# Power_Board_CRoach.net
KiCad netlist of a schematic drawn in EAGLE
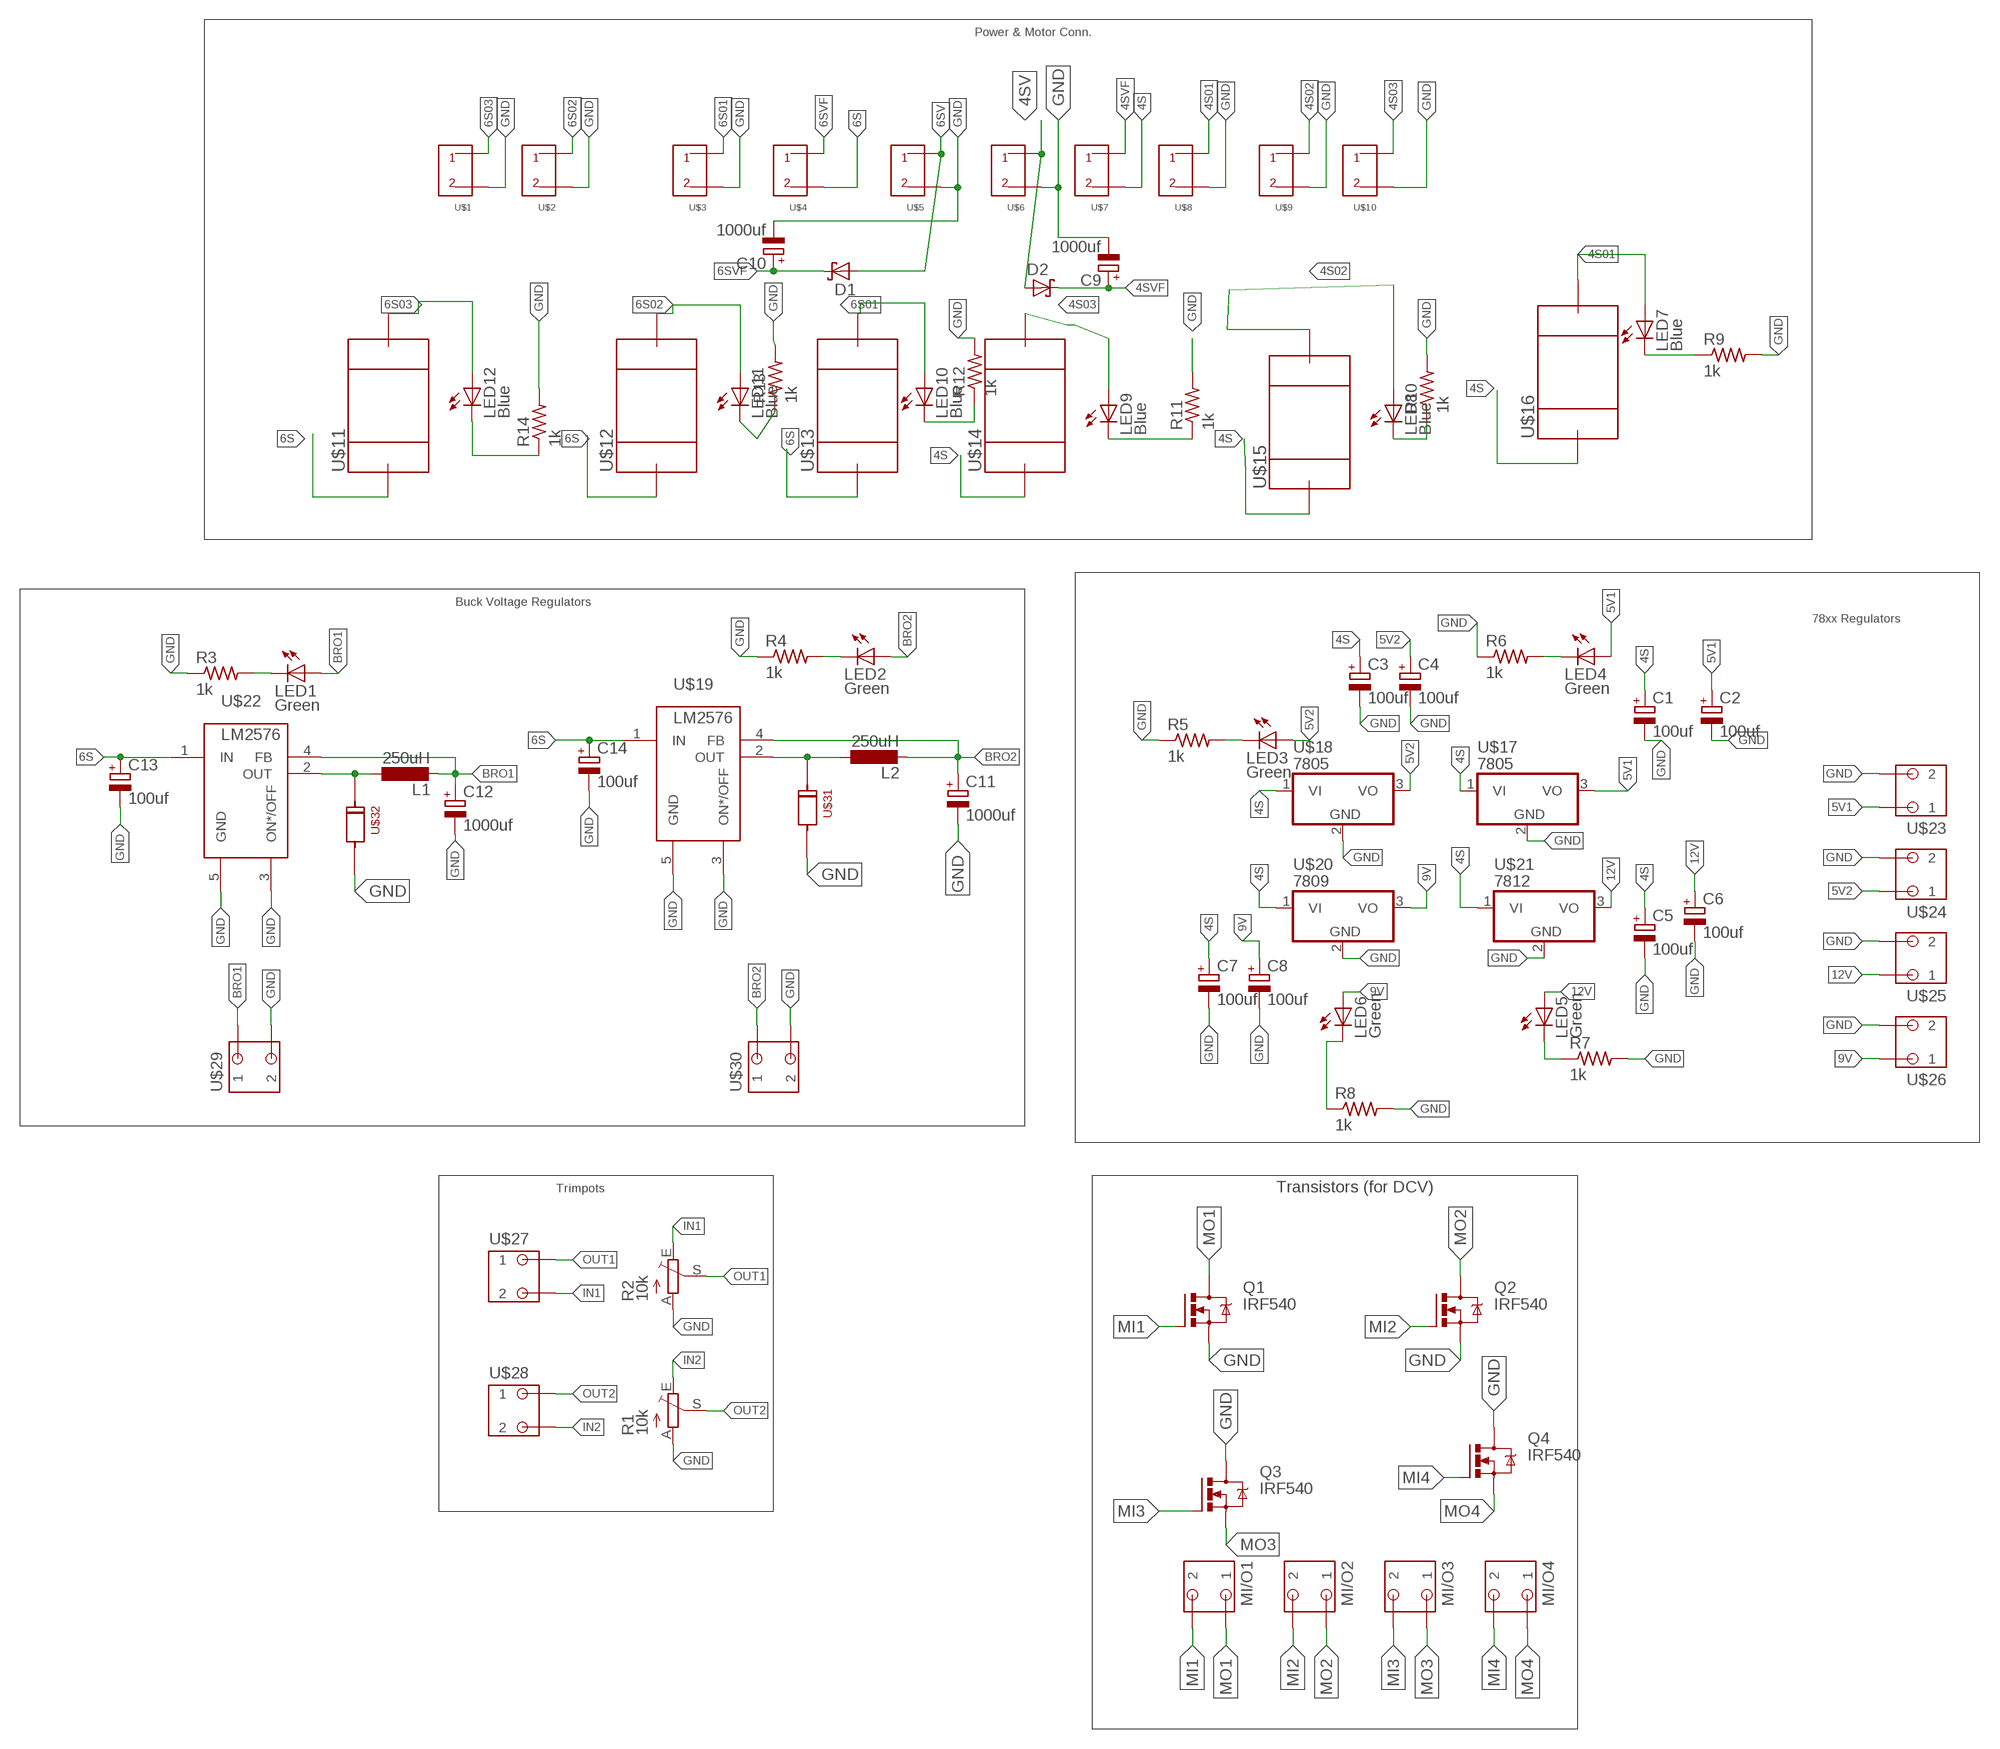
[diagram p0: schematic, sheet 1]

(export (version "E")
  (design (tool "Eeschema 10.0.6"))
  (components
    (comp (ref "C1")
      (value "100uf")
      (footprint "eagle-import:E2-5")
      (libsource (lib "eagle-import") (part "CPOL-EUE2-5"))
    )
    (comp (ref "C2")
      (value "100uf")
      (footprint "eagle-import:E2-5")
      (libsource (lib "eagle-import") (part "CPOL-EUE2-5"))
    )
    (comp (ref "C3")
      (value "100uf")
      (footprint "eagle-import:E2-5")
      (libsource (lib "eagle-import") (part "CPOL-EUE2-5"))
    )
    (comp (ref "C4")
      (value "100uf")
      (footprint "eagle-import:E2-5")
      (libsource (lib "eagle-import") (part "CPOL-EUE2-5"))
    )
    (comp (ref "C5")
      (value "100uf")
      (footprint "eagle-import:E2-5")
      (libsource (lib "eagle-import") (part "CPOL-EUE2-5"))
    )
    (comp (ref "C6")
      (value "100uf")
      (footprint "eagle-import:E2-5")
      (libsource (lib "eagle-import") (part "CPOL-EUE2-5"))
    )
    (comp (ref "C7")
      (value "100uf")
      (footprint "eagle-import:E2-5")
      (libsource (lib "eagle-import") (part "CPOL-EUE2-5"))
    )
    (comp (ref "C8")
      (value "100uf")
      (footprint "eagle-import:E2-5")
      (libsource (lib "eagle-import") (part "CPOL-EUE2-5"))
    )
    (comp (ref "C9")
      (value "1000uf")
      (footprint "eagle-import:E7,5-16")
      (libsource (lib "eagle-import") (part "CPOL-EUE7.5-16"))
    )
    (comp (ref "C10")
      (value "1000uf")
      (footprint "eagle-import:E7,5-16")
      (libsource (lib "eagle-import") (part "CPOL-EUE7.5-16"))
    )
    (comp (ref "C11")
      (value "1000uf")
      (footprint "eagle-import:E7,5-16")
      (libsource (lib "eagle-import") (part "CPOL-EUE7.5-16"))
    )
    (comp (ref "C12")
      (value "1000uf")
      (footprint "eagle-import:E7,5-16")
      (libsource (lib "eagle-import") (part "CPOL-EUE7.5-16"))
    )
    (comp (ref "C13")
      (value "100uf")
      (footprint "eagle-import:E2,5-5")
      (libsource (lib "eagle-import") (part "CPOL-EUE2.5-5"))
    )
    (comp (ref "C14")
      (value "100uf")
      (footprint "eagle-import:E2,5-5")
      (libsource (lib "eagle-import") (part "CPOL-EUE2.5-5"))
    )
    (comp (ref "D1")
      (value "SCHOTTKY-DIODEP6T15")
      (footprint "eagle-import:P6T15")
      (libsource (lib "eagle-import") (part "SCHOTTKY-DIODEP6T15"))
    )
    (comp (ref "D2")
      (value "SCHOTTKY-DIODEP6T15")
      (footprint "eagle-import:P6T15")
      (libsource (lib "eagle-import") (part "SCHOTTKY-DIODEP6T15"))
    )
    (comp (ref "L1")
      (value "250uH")
      (footprint "eagle-import:0204_7")
      (libsource (lib "eagle-import") (part "L-EU0204/7"))
    )
    (comp (ref "L2")
      (value "250uH")
      (footprint "eagle-import:0204_7")
      (libsource (lib "eagle-import") (part "L-EU0204/7"))
    )
    (comp (ref "LED1")
      (value "Green")
      (footprint "eagle-import:LED5MM")
      (libsource (lib "eagle-import") (part "LED5MM"))
    )
    (comp (ref "LED2")
      (value "Green")
      (footprint "eagle-import:LED5MM")
      (libsource (lib "eagle-import") (part "LED5MM"))
    )
    (comp (ref "LED3")
      (value "Green")
      (footprint "eagle-import:LED5MM")
      (libsource (lib "eagle-import") (part "LED5MM"))
    )
    (comp (ref "LED4")
      (value "Green")
      (footprint "eagle-import:LED5MM")
      (libsource (lib "eagle-import") (part "LED5MM"))
    )
    (comp (ref "LED5")
      (value "Green")
      (footprint "eagle-import:LED5MM")
      (libsource (lib "eagle-import") (part "LED5MM"))
    )
    (comp (ref "LED6")
      (value "Green")
      (footprint "eagle-import:LED5MM")
      (libsource (lib "eagle-import") (part "LED5MM"))
    )
    (comp (ref "LED7")
      (value "Blue")
      (footprint "eagle-import:LED5MM")
      (libsource (lib "eagle-import") (part "LED5MM"))
    )
    (comp (ref "LED8")
      (value "Blue")
      (footprint "eagle-import:LED5MM")
      (libsource (lib "eagle-import") (part "LED5MM"))
    )
    (comp (ref "LED9")
      (value "Blue")
      (footprint "eagle-import:LED5MM")
      (libsource (lib "eagle-import") (part "LED5MM"))
    )
    (comp (ref "LED10")
      (value "Blue")
      (footprint "eagle-import:LED5MM")
      (libsource (lib "eagle-import") (part "LED5MM"))
    )
    (comp (ref "LED11")
      (value "Blue")
      (footprint "eagle-import:LED5MM")
      (libsource (lib "eagle-import") (part "LED5MM"))
    )
    (comp (ref "LED12")
      (value "Blue")
      (footprint "eagle-import:LED5MM")
      (libsource (lib "eagle-import") (part "LED5MM"))
    )
    (comp (ref "MI/O1")
      (value "SPTBB2-A2")
      (footprint "eagle-import:SPTB")
      (libsource (lib "eagle-import") (part "SPTBB2-A2"))
    )
    (comp (ref "MI/O2")
      (value "SPTBB2-A2")
      (footprint "eagle-import:SPTB")
      (libsource (lib "eagle-import") (part "SPTBB2-A2"))
    )
    (comp (ref "MI/O3")
      (value "SPTBB2-A2")
      (footprint "eagle-import:SPTB")
      (libsource (lib "eagle-import") (part "SPTBB2-A2"))
    )
    (comp (ref "MI/O4")
      (value "SPTBB2-A2")
      (footprint "eagle-import:SPTB")
      (libsource (lib "eagle-import") (part "SPTBB2-A2"))
    )
    (comp (ref "Q1")
      (value "IRF540")
      (footprint "eagle-import:TO220BV")
      (libsource (lib "eagle-import") (part "IRF540"))
    )
    (comp (ref "Q2")
      (value "IRF540")
      (footprint "eagle-import:TO220BV")
      (libsource (lib "eagle-import") (part "IRF540"))
    )
    (comp (ref "Q3")
      (value "IRF540")
      (footprint "eagle-import:TO220BV")
      (libsource (lib "eagle-import") (part "IRF540"))
    )
    (comp (ref "Q4")
      (value "IRF540")
      (footprint "eagle-import:TO220BV")
      (libsource (lib "eagle-import") (part "IRF540"))
    )
    (comp (ref "R1")
      (value "10k")
      (footprint "eagle-import:CA6V")
      (libsource (lib "eagle-import") (part "TRIM_EU-CA6V"))
    )
    (comp (ref "R2")
      (value "10k")
      (footprint "eagle-import:CA6V")
      (libsource (lib "eagle-import") (part "TRIM_EU-CA6V"))
    )
    (comp (ref "R3")
      (value "1k")
      (footprint "eagle-import:0204_7")
      (libsource (lib "eagle-import") (part "R-US_0204/7"))
    )
    (comp (ref "R4")
      (value "1k")
      (footprint "eagle-import:0204_7")
      (libsource (lib "eagle-import") (part "R-US_0204/7"))
    )
    (comp (ref "R5")
      (value "1k")
      (footprint "eagle-import:0204_7")
      (libsource (lib "eagle-import") (part "R-US_0204/7"))
    )
    (comp (ref "R6")
      (value "1k")
      (footprint "eagle-import:0204_7")
      (libsource (lib "eagle-import") (part "R-US_0204/7"))
    )
    (comp (ref "R7")
      (value "1k")
      (footprint "eagle-import:0204_7")
      (libsource (lib "eagle-import") (part "R-US_0204/7"))
    )
    (comp (ref "R8")
      (value "1k")
      (footprint "eagle-import:0204_7")
      (libsource (lib "eagle-import") (part "R-US_0204/7"))
    )
    (comp (ref "R9")
      (value "1k")
      (footprint "eagle-import:0204_7")
      (libsource (lib "eagle-import") (part "R-US_0204/7"))
    )
    (comp (ref "R10")
      (value "1k")
      (footprint "eagle-import:0204_7")
      (libsource (lib "eagle-import") (part "R-US_0204/7"))
    )
    (comp (ref "R11")
      (value "1k")
      (footprint "eagle-import:0204_7")
      (libsource (lib "eagle-import") (part "R-US_0204/7"))
    )
    (comp (ref "R12")
      (value "1k")
      (footprint "eagle-import:0204_7")
      (libsource (lib "eagle-import") (part "R-US_0204/7"))
    )
    (comp (ref "R13")
      (value "1k")
      (footprint "eagle-import:0204_7")
      (libsource (lib "eagle-import") (part "R-US_0204/7"))
    )
    (comp (ref "R14")
      (value "1k")
      (footprint "eagle-import:0204_7")
      (libsource (lib "eagle-import") (part "R-US_0204/7"))
    )
    (comp (ref "U$1")
      (value "SCREW_XT-60")
      (footprint "eagle-import:SCREW_XT-60")
      (libsource (lib "eagle-import") (part "SCREW_XT-60"))
    )
    (comp (ref "U$2")
      (value "SCREW_XT-60")
      (footprint "eagle-import:SCREW_XT-60")
      (libsource (lib "eagle-import") (part "SCREW_XT-60"))
    )
    (comp (ref "U$3")
      (value "SCREW_XT-60")
      (footprint "eagle-import:SCREW_XT-60")
      (libsource (lib "eagle-import") (part "SCREW_XT-60"))
    )
    (comp (ref "U$4")
      (value "SCREW_XT-60")
      (footprint "eagle-import:SCREW_XT-60")
      (libsource (lib "eagle-import") (part "SCREW_XT-60"))
    )
    (comp (ref "U$5")
      (value "SCREW_XT-60")
      (footprint "eagle-import:SCREW_XT-60")
      (libsource (lib "eagle-import") (part "SCREW_XT-60"))
    )
    (comp (ref "U$6")
      (value "SCREW_XT-60")
      (footprint "eagle-import:SCREW_XT-60")
      (libsource (lib "eagle-import") (part "SCREW_XT-60"))
    )
    (comp (ref "U$7")
      (value "SCREW_XT-60")
      (footprint "eagle-import:SCREW_XT-60")
      (libsource (lib "eagle-import") (part "SCREW_XT-60"))
    )
    (comp (ref "U$8")
      (value "SCREW_XT-60")
      (footprint "eagle-import:SCREW_XT-60")
      (libsource (lib "eagle-import") (part "SCREW_XT-60"))
    )
    (comp (ref "U$9")
      (value "SCREW_XT-60")
      (footprint "eagle-import:SCREW_XT-60")
      (libsource (lib "eagle-import") (part "SCREW_XT-60"))
    )
    (comp (ref "U$10")
      (value "SCREW_XT-60")
      (footprint "eagle-import:SCREW_XT-60")
      (libsource (lib "eagle-import") (part "SCREW_XT-60"))
    )
    (comp (ref "U$11")
      (value "CPT-FUSE")
      (footprint "eagle-import:CPT-FUSES")
      (libsource (lib "eagle-import") (part "CPT-FUSE"))
    )
    (comp (ref "U$12")
      (value "CPT-FUSE")
      (footprint "eagle-import:CPT-FUSES")
      (libsource (lib "eagle-import") (part "CPT-FUSE"))
    )
    (comp (ref "U$13")
      (value "CPT-FUSE")
      (footprint "eagle-import:CPT-FUSES")
      (libsource (lib "eagle-import") (part "CPT-FUSE"))
    )
    (comp (ref "U$14")
      (value "CPT-FUSE")
      (footprint "eagle-import:CPT-FUSES")
      (libsource (lib "eagle-import") (part "CPT-FUSE"))
    )
    (comp (ref "U$15")
      (value "CPT-FUSE")
      (footprint "eagle-import:CPT-FUSES")
      (libsource (lib "eagle-import") (part "CPT-FUSE"))
    )
    (comp (ref "U$16")
      (value "CPT-FUSE")
      (footprint "eagle-import:CPT-FUSES")
      (libsource (lib "eagle-import") (part "CPT-FUSE"))
    )
    (comp (ref "U$17")
      (value "7805")
      (footprint "eagle-import:78XX")
      (libsource (lib "eagle-import") (part "7805"))
    )
    (comp (ref "U$18")
      (value "7805")
      (footprint "eagle-import:78XX")
      (libsource (lib "eagle-import") (part "7805"))
    )
    (comp (ref "U$19")
      (value "LM2576")
      (footprint "eagle-import:LM2576")
      (libsource (lib "eagle-import") (part "LM2576"))
    )
    (comp (ref "U$20")
      (value "7809")
      (footprint "eagle-import:78XX")
      (libsource (lib "eagle-import") (part "7809"))
    )
    (comp (ref "U$21")
      (value "7812")
      (footprint "eagle-import:78XX")
      (libsource (lib "eagle-import") (part "7812"))
    )
    (comp (ref "U$22")
      (value "LM2576")
      (footprint "eagle-import:LM2576")
      (libsource (lib "eagle-import") (part "LM2576"))
    )
    (comp (ref "U$23")
      (value "SPTBB2-A1")
      (footprint "eagle-import:SPTB")
      (libsource (lib "eagle-import") (part "SPTBB2-A1"))
    )
    (comp (ref "U$24")
      (value "SPTBB2-A1")
      (footprint "eagle-import:SPTB")
      (libsource (lib "eagle-import") (part "SPTBB2-A1"))
    )
    (comp (ref "U$25")
      (value "SPTBA2-B1")
      (footprint "eagle-import:SPTB")
      (libsource (lib "eagle-import") (part "SPTBA2-B1"))
    )
    (comp (ref "U$26")
      (value "SPTBA2-B1")
      (footprint "eagle-import:SPTB")
      (libsource (lib "eagle-import") (part "SPTBA2-B1"))
    )
    (comp (ref "U$27")
      (value "SPTBB2-A1")
      (footprint "eagle-import:SPTB")
      (libsource (lib "eagle-import") (part "SPTBB2-A1"))
    )
    (comp (ref "U$28")
      (value "SPTBB2-A1")
      (footprint "eagle-import:SPTB")
      (libsource (lib "eagle-import") (part "SPTBB2-A1"))
    )
    (comp (ref "U$29")
      (value "SPTBA2-B1")
      (footprint "eagle-import:SPTB")
      (libsource (lib "eagle-import") (part "SPTBA2-B1"))
    )
    (comp (ref "U$30")
      (value "SPTBA2-B1")
      (footprint "eagle-import:SPTB")
      (libsource (lib "eagle-import") (part "SPTBA2-B1"))
    )
    (comp (ref "U$31")
      (value "1N5822")
      (footprint "eagle-import:1N5822")
      (libsource (lib "eagle-import") (part "1N5822"))
    )
    (comp (ref "U$32")
      (value "1N5822")
      (footprint "eagle-import:1N5822")
      (libsource (lib "eagle-import") (part "1N5822"))
    )
  )
  (nets
    (net (code "1") (name "4S") (class "Default")
      (node (ref "C1") (pin "+") (pinfunction "+_+") (pintype "passive"))
      (node (ref "C3") (pin "+") (pinfunction "+_+") (pintype "passive"))
      (node (ref "C5") (pin "+") (pinfunction "+_+") (pintype "passive"))
      (node (ref "C7") (pin "+") (pinfunction "+_+") (pintype "passive"))
      (node (ref "U$14") (pin "P$1") (pinfunction "P$1_P$1") (pintype "bidirectional"))
      (node (ref "U$15") (pin "P$1") (pinfunction "P$1_P$1") (pintype "bidirectional"))
      (node (ref "U$16") (pin "P$1") (pinfunction "P$1_P$1") (pintype "bidirectional"))
      (node (ref "U$17") (pin "1") (pinfunction "VI_1") (pintype "input"))
      (node (ref "U$18") (pin "1") (pinfunction "VI_1") (pintype "input"))
      (node (ref "U$20") (pin "1") (pinfunction "VI_1") (pintype "input"))
      (node (ref "U$21") (pin "1") (pinfunction "VI_1") (pintype "input"))
      (node (ref "U$7") (pin "P$2") (pinfunction "P$2_P$2") (pintype "bidirectional"))
    )
    (net (code "2") (name "4S01") (class "Default")
      (node (ref "LED7") (pin "A") (pinfunction "A_A") (pintype "passive"))
      (node (ref "U$16") (pin "P$2") (pinfunction "P$2_P$2") (pintype "bidirectional"))
      (node (ref "U$8") (pin "P$1") (pinfunction "P$1_P$1") (pintype "bidirectional"))
    )
    (net (code "3") (name "4S02") (class "Default")
      (node (ref "LED8") (pin "A") (pinfunction "A_A") (pintype "passive"))
      (node (ref "U$15") (pin "P$2") (pinfunction "P$2_P$2") (pintype "bidirectional"))
      (node (ref "U$9") (pin "P$1") (pinfunction "P$1_P$1") (pintype "bidirectional"))
    )
    (net (code "4") (name "4S03") (class "Default")
      (node (ref "LED9") (pin "A") (pinfunction "A_A") (pintype "passive"))
      (node (ref "U$10") (pin "P$1") (pinfunction "P$1_P$1") (pintype "bidirectional"))
      (node (ref "U$14") (pin "P$2") (pinfunction "P$2_P$2") (pintype "bidirectional"))
    )
    (net (code "5") (name "4SV") (class "Default")
      (node (ref "D2") (pin "A") (pinfunction "A_A") (pintype "passive"))
      (node (ref "U$6") (pin "P$1") (pinfunction "P$1_P$1") (pintype "bidirectional"))
    )
    (net (code "6") (name "4SVF") (class "Default")
      (node (ref "C9") (pin "+") (pinfunction "+_+") (pintype "passive"))
      (node (ref "D2") (pin "C") (pinfunction "C_C") (pintype "passive"))
      (node (ref "U$7") (pin "P$1") (pinfunction "P$1_P$1") (pintype "bidirectional"))
    )
    (net (code "7") (name "5V1") (class "Default")
      (node (ref "C2") (pin "+") (pinfunction "+_+") (pintype "passive"))
      (node (ref "LED4") (pin "A") (pinfunction "A_A") (pintype "passive"))
      (node (ref "U$17") (pin "3") (pinfunction "VO_3") (pintype "passive"))
      (node (ref "U$23") (pin "B2") (pinfunction "1_B2") (pintype "bidirectional"))
    )
    (net (code "8") (name "5V2") (class "Default")
      (node (ref "C4") (pin "+") (pinfunction "+_+") (pintype "passive"))
      (node (ref "LED3") (pin "A") (pinfunction "A_A") (pintype "passive"))
      (node (ref "U$18") (pin "3") (pinfunction "VO_3") (pintype "passive"))
      (node (ref "U$24") (pin "B2") (pinfunction "1_B2") (pintype "bidirectional"))
    )
    (net (code "9") (name "6S") (class "Default")
      (node (ref "C13") (pin "+") (pinfunction "+_+") (pintype "passive"))
      (node (ref "C14") (pin "+") (pinfunction "+_+") (pintype "passive"))
      (node (ref "U$11") (pin "P$1") (pinfunction "P$1_P$1") (pintype "bidirectional"))
      (node (ref "U$12") (pin "P$1") (pinfunction "P$1_P$1") (pintype "bidirectional"))
      (node (ref "U$13") (pin "P$1") (pinfunction "P$1_P$1") (pintype "bidirectional"))
      (node (ref "U$19") (pin "1") (pinfunction "IN_1") (pintype "bidirectional"))
      (node (ref "U$22") (pin "1") (pinfunction "IN_1") (pintype "bidirectional"))
      (node (ref "U$4") (pin "P$2") (pinfunction "P$2_P$2") (pintype "bidirectional"))
    )
    (net (code "10") (name "6S01") (class "Default")
      (node (ref "LED10") (pin "A") (pinfunction "A_A") (pintype "passive"))
      (node (ref "U$13") (pin "P$2") (pinfunction "P$2_P$2") (pintype "bidirectional"))
      (node (ref "U$3") (pin "P$1") (pinfunction "P$1_P$1") (pintype "bidirectional"))
    )
    (net (code "11") (name "6S02") (class "Default")
      (node (ref "LED11") (pin "A") (pinfunction "A_A") (pintype "passive"))
      (node (ref "U$12") (pin "P$2") (pinfunction "P$2_P$2") (pintype "bidirectional"))
      (node (ref "U$2") (pin "P$1") (pinfunction "P$1_P$1") (pintype "bidirectional"))
    )
    (net (code "12") (name "6S03") (class "Default")
      (node (ref "LED12") (pin "A") (pinfunction "A_A") (pintype "passive"))
      (node (ref "U$1") (pin "P$1") (pinfunction "P$1_P$1") (pintype "bidirectional"))
      (node (ref "U$11") (pin "P$2") (pinfunction "P$2_P$2") (pintype "bidirectional"))
    )
    (net (code "13") (name "6SV") (class "Default")
      (node (ref "D1") (pin "A") (pinfunction "A_A") (pintype "passive"))
      (node (ref "U$5") (pin "P$1") (pinfunction "P$1_P$1") (pintype "bidirectional"))
    )
    (net (code "14") (name "6SVF") (class "Default")
      (node (ref "C10") (pin "+") (pinfunction "+_+") (pintype "passive"))
      (node (ref "D1") (pin "C") (pinfunction "C_C") (pintype "passive"))
      (node (ref "U$4") (pin "P$1") (pinfunction "P$1_P$1") (pintype "bidirectional"))
    )
    (net (code "15") (name "9V") (class "Default")
      (node (ref "C8") (pin "+") (pinfunction "+_+") (pintype "passive"))
      (node (ref "LED6") (pin "A") (pinfunction "A_A") (pintype "passive"))
      (node (ref "U$20") (pin "3") (pinfunction "VO_3") (pintype "passive"))
      (node (ref "U$26") (pin "A2") (pinfunction "1_A2") (pintype "bidirectional"))
    )
    (net (code "16") (name "12V") (class "Default")
      (node (ref "C6") (pin "+") (pinfunction "+_+") (pintype "passive"))
      (node (ref "LED5") (pin "A") (pinfunction "A_A") (pintype "passive"))
      (node (ref "U$21") (pin "3") (pinfunction "VO_3") (pintype "passive"))
      (node (ref "U$25") (pin "A2") (pinfunction "1_A2") (pintype "bidirectional"))
    )
    (net (code "17") (name "BRO1") (class "Default")
      (node (ref "C12") (pin "+") (pinfunction "+_+") (pintype "passive"))
      (node (ref "L1") (pin "2") (pinfunction "2_2") (pintype "passive"))
      (node (ref "LED1") (pin "A") (pinfunction "A_A") (pintype "passive"))
      (node (ref "U$22") (pin "4") (pinfunction "FB_4") (pintype "bidirectional"))
      (node (ref "U$29") (pin "A2") (pinfunction "1_A2") (pintype "bidirectional"))
    )
    (net (code "18") (name "BRO2") (class "Default")
      (node (ref "C11") (pin "+") (pinfunction "+_+") (pintype "passive"))
      (node (ref "L2") (pin "2") (pinfunction "2_2") (pintype "passive"))
      (node (ref "LED2") (pin "A") (pinfunction "A_A") (pintype "passive"))
      (node (ref "U$19") (pin "4") (pinfunction "FB_4") (pintype "bidirectional"))
      (node (ref "U$30") (pin "A2") (pinfunction "1_A2") (pintype "bidirectional"))
    )
    (net (code "19") (name "GND") (class "Default")
      (node (ref "C1") (pin "-") (pinfunction "-_-") (pintype "passive"))
      (node (ref "C10") (pin "-") (pinfunction "-_-") (pintype "passive"))
      (node (ref "C11") (pin "-") (pinfunction "-_-") (pintype "passive"))
      (node (ref "C12") (pin "-") (pinfunction "-_-") (pintype "passive"))
      (node (ref "C13") (pin "-") (pinfunction "-_-") (pintype "passive"))
      (node (ref "C14") (pin "-") (pinfunction "-_-") (pintype "passive"))
      (node (ref "C2") (pin "-") (pinfunction "-_-") (pintype "passive"))
      (node (ref "C3") (pin "-") (pinfunction "-_-") (pintype "passive"))
      (node (ref "C4") (pin "-") (pinfunction "-_-") (pintype "passive"))
      (node (ref "C5") (pin "-") (pinfunction "-_-") (pintype "passive"))
      (node (ref "C6") (pin "-") (pinfunction "-_-") (pintype "passive"))
      (node (ref "C7") (pin "-") (pinfunction "-_-") (pintype "passive"))
      (node (ref "C8") (pin "-") (pinfunction "-_-") (pintype "passive"))
      (node (ref "C9") (pin "-") (pinfunction "-_-") (pintype "passive"))
      (node (ref "Q1") (pin "S") (pinfunction "S_S") (pintype "passive"))
      (node (ref "Q2") (pin "S") (pinfunction "S_S") (pintype "passive"))
      (node (ref "Q3") (pin "D") (pinfunction "D_D") (pintype "passive"))
      (node (ref "Q4") (pin "D") (pinfunction "D_D") (pintype "passive"))
      (node (ref "R1") (pin "A") (pinfunction "A_A") (pintype "passive"))
      (node (ref "R10") (pin "2") (pinfunction "2_2") (pintype "passive"))
      (node (ref "R11") (pin "2") (pinfunction "2_2") (pintype "passive"))
      (node (ref "R12") (pin "2") (pinfunction "2_2") (pintype "passive"))
      (node (ref "R13") (pin "2") (pinfunction "2_2") (pintype "passive"))
      (node (ref "R14") (pin "2") (pinfunction "2_2") (pintype "passive"))
      (node (ref "R2") (pin "A") (pinfunction "A_A") (pintype "passive"))
      (node (ref "R3") (pin "1") (pinfunction "1_1") (pintype "passive"))
      (node (ref "R4") (pin "1") (pinfunction "1_1") (pintype "passive"))
      (node (ref "R5") (pin "1") (pinfunction "1_1") (pintype "passive"))
      (node (ref "R6") (pin "1") (pinfunction "1_1") (pintype "passive"))
      (node (ref "R7") (pin "2") (pinfunction "2_2") (pintype "passive"))
      (node (ref "R8") (pin "2") (pinfunction "2_2") (pintype "passive"))
      (node (ref "R9") (pin "2") (pinfunction "2_2") (pintype "passive"))
      (node (ref "U$1") (pin "P$2") (pinfunction "P$2_P$2") (pintype "bidirectional"))
      (node (ref "U$10") (pin "P$2") (pinfunction "P$2_P$2") (pintype "bidirectional"))
      (node (ref "U$17") (pin "2") (pinfunction "GND_2") (pintype "passive"))
      (node (ref "U$18") (pin "2") (pinfunction "GND_2") (pintype "passive"))
      (node (ref "U$19") (pin "3") (pinfunction "ON*/OFF_3") (pintype "bidirectional"))
      (node (ref "U$19") (pin "5") (pinfunction "GND_5") (pintype "bidirectional"))
      (node (ref "U$2") (pin "P$2") (pinfunction "P$2_P$2") (pintype "bidirectional"))
      (node (ref "U$20") (pin "2") (pinfunction "GND_2") (pintype "passive"))
      (node (ref "U$21") (pin "2") (pinfunction "GND_2") (pintype "passive"))
      (node (ref "U$22") (pin "3") (pinfunction "ON*/OFF_3") (pintype "bidirectional"))
      (node (ref "U$22") (pin "5") (pinfunction "GND_5") (pintype "bidirectional"))
      (node (ref "U$23") (pin "A1") (pinfunction "2_A1") (pintype "bidirectional"))
      (node (ref "U$24") (pin "A1") (pinfunction "2_A1") (pintype "bidirectional"))
      (node (ref "U$25") (pin "B1") (pinfunction "2_B1") (pintype "bidirectional"))
      (node (ref "U$26") (pin "B1") (pinfunction "2_B1") (pintype "bidirectional"))
      (node (ref "U$29") (pin "B1") (pinfunction "2_B1") (pintype "bidirectional"))
      (node (ref "U$3") (pin "P$2") (pinfunction "P$2_P$2") (pintype "bidirectional"))
      (node (ref "U$30") (pin "B1") (pinfunction "2_B1") (pintype "bidirectional"))
      (node (ref "U$31") (pin "-") (pinfunction "-_-") (pintype "bidirectional"))
      (node (ref "U$32") (pin "-") (pinfunction "-_-") (pintype "bidirectional"))
      (node (ref "U$5") (pin "P$2") (pinfunction "P$2_P$2") (pintype "bidirectional"))
      (node (ref "U$6") (pin "P$2") (pinfunction "P$2_P$2") (pintype "bidirectional"))
      (node (ref "U$8") (pin "P$2") (pinfunction "P$2_P$2") (pintype "bidirectional"))
      (node (ref "U$9") (pin "P$2") (pinfunction "P$2_P$2") (pintype "bidirectional"))
    )
    (net (code "20") (name "IN1") (class "Default")
      (node (ref "R2") (pin "E") (pinfunction "E_E") (pintype "passive"))
      (node (ref "U$27") (pin "A1") (pinfunction "2_A1") (pintype "bidirectional"))
    )
    (net (code "21") (name "IN2") (class "Default")
      (node (ref "R1") (pin "E") (pinfunction "E_E") (pintype "passive"))
      (node (ref "U$28") (pin "A1") (pinfunction "2_A1") (pintype "bidirectional"))
    )
    (net (code "22") (name "MI1") (class "Default")
      (node (ref "MI/O1") (pin "A2") (pinfunction "2_A2") (pintype "bidirectional"))
      (node (ref "Q1") (pin "G") (pinfunction "G_G") (pintype "passive"))
    )
    (net (code "23") (name "MI2") (class "Default")
      (node (ref "MI/O2") (pin "A2") (pinfunction "2_A2") (pintype "bidirectional"))
      (node (ref "Q2") (pin "G") (pinfunction "G_G") (pintype "passive"))
    )
    (net (code "24") (name "MI3") (class "Default")
      (node (ref "MI/O3") (pin "A2") (pinfunction "2_A2") (pintype "bidirectional"))
      (node (ref "Q3") (pin "G") (pinfunction "G_G") (pintype "passive"))
    )
    (net (code "25") (name "MI4") (class "Default")
      (node (ref "MI/O4") (pin "A2") (pinfunction "2_A2") (pintype "bidirectional"))
      (node (ref "Q4") (pin "G") (pinfunction "G_G") (pintype "passive"))
    )
    (net (code "26") (name "MO1") (class "Default")
      (node (ref "MI/O1") (pin "B2") (pinfunction "1_B2") (pintype "bidirectional"))
      (node (ref "Q1") (pin "D") (pinfunction "D_D") (pintype "passive"))
    )
    (net (code "27") (name "MO2") (class "Default")
      (node (ref "MI/O2") (pin "B2") (pinfunction "1_B2") (pintype "bidirectional"))
      (node (ref "Q2") (pin "D") (pinfunction "D_D") (pintype "passive"))
    )
    (net (code "28") (name "MO3") (class "Default")
      (node (ref "MI/O3") (pin "B2") (pinfunction "1_B2") (pintype "bidirectional"))
      (node (ref "Q3") (pin "S") (pinfunction "S_S") (pintype "passive"))
    )
    (net (code "29") (name "MO4") (class "Default")
      (node (ref "MI/O4") (pin "B2") (pinfunction "1_B2") (pintype "bidirectional"))
      (node (ref "Q4") (pin "S") (pinfunction "S_S") (pintype "passive"))
    )
    (net (code "30") (name "Net-(LED1-C)") (class "Default")
      (node (ref "LED1") (pin "K") (pinfunction "C_K") (pintype "passive"))
      (node (ref "R3") (pin "2") (pinfunction "2_2") (pintype "passive"))
    )
    (net (code "31") (name "Net-(LED2-C)") (class "Default")
      (node (ref "LED2") (pin "K") (pinfunction "C_K") (pintype "passive"))
      (node (ref "R4") (pin "2") (pinfunction "2_2") (pintype "passive"))
    )
    (net (code "32") (name "Net-(LED3-C)") (class "Default")
      (node (ref "LED3") (pin "K") (pinfunction "C_K") (pintype "passive"))
      (node (ref "R5") (pin "2") (pinfunction "2_2") (pintype "passive"))
    )
    (net (code "33") (name "Net-(LED4-C)") (class "Default")
      (node (ref "LED4") (pin "K") (pinfunction "C_K") (pintype "passive"))
      (node (ref "R6") (pin "2") (pinfunction "2_2") (pintype "passive"))
    )
    (net (code "34") (name "Net-(LED5-C)") (class "Default")
      (node (ref "LED5") (pin "K") (pinfunction "C_K") (pintype "passive"))
      (node (ref "R7") (pin "1") (pinfunction "1_1") (pintype "passive"))
    )
    (net (code "35") (name "Net-(LED6-C)") (class "Default")
      (node (ref "LED6") (pin "K") (pinfunction "C_K") (pintype "passive"))
      (node (ref "R8") (pin "1") (pinfunction "1_1") (pintype "passive"))
    )
    (net (code "36") (name "Net-(LED7-C)") (class "Default")
      (node (ref "LED7") (pin "K") (pinfunction "C_K") (pintype "passive"))
      (node (ref "R9") (pin "1") (pinfunction "1_1") (pintype "passive"))
    )
    (net (code "37") (name "Net-(LED8-C)") (class "Default")
      (node (ref "LED8") (pin "K") (pinfunction "C_K") (pintype "passive"))
      (node (ref "R10") (pin "1") (pinfunction "1_1") (pintype "passive"))
    )
    (net (code "38") (name "Net-(LED9-C)") (class "Default")
      (node (ref "LED9") (pin "K") (pinfunction "C_K") (pintype "passive"))
      (node (ref "R11") (pin "1") (pinfunction "1_1") (pintype "passive"))
    )
    (net (code "39") (name "Net-(LED10-C)") (class "Default")
      (node (ref "LED10") (pin "K") (pinfunction "C_K") (pintype "passive"))
      (node (ref "R12") (pin "1") (pinfunction "1_1") (pintype "passive"))
    )
    (net (code "40") (name "Net-(LED11-C)") (class "Default")
      (node (ref "LED11") (pin "K") (pinfunction "C_K") (pintype "passive"))
      (node (ref "R13") (pin "1") (pinfunction "1_1") (pintype "passive"))
    )
    (net (code "41") (name "Net-(LED12-C)") (class "Default")
      (node (ref "LED12") (pin "K") (pinfunction "C_K") (pintype "passive"))
      (node (ref "R14") (pin "1") (pinfunction "1_1") (pintype "passive"))
    )
    (net (code "42") (name "Net-(U$19-OUT)") (class "Default")
      (node (ref "L2") (pin "1") (pinfunction "1_1") (pintype "passive"))
      (node (ref "U$19") (pin "2") (pinfunction "OUT_2") (pintype "bidirectional"))
      (node (ref "U$31") (pin "+") (pinfunction "+_+") (pintype "bidirectional"))
    )
    (net (code "43") (name "Net-(U$22-OUT)") (class "Default")
      (node (ref "L1") (pin "1") (pinfunction "1_1") (pintype "passive"))
      (node (ref "U$22") (pin "2") (pinfunction "OUT_2") (pintype "bidirectional"))
      (node (ref "U$32") (pin "+") (pinfunction "+_+") (pintype "bidirectional"))
    )
    (net (code "44") (name "OUT1") (class "Default")
      (node (ref "R2") (pin "S") (pinfunction "S_S") (pintype "passive"))
      (node (ref "U$27") (pin "B2") (pinfunction "1_B2") (pintype "bidirectional"))
    )
    (net (code "45") (name "OUT2") (class "Default")
      (node (ref "R1") (pin "S") (pinfunction "S_S") (pintype "passive"))
      (node (ref "U$28") (pin "B2") (pinfunction "1_B2") (pintype "bidirectional"))
    )
  )
)
